# Digital_Input.net
KiCad netlist of a schematic drawn in Altium Designer
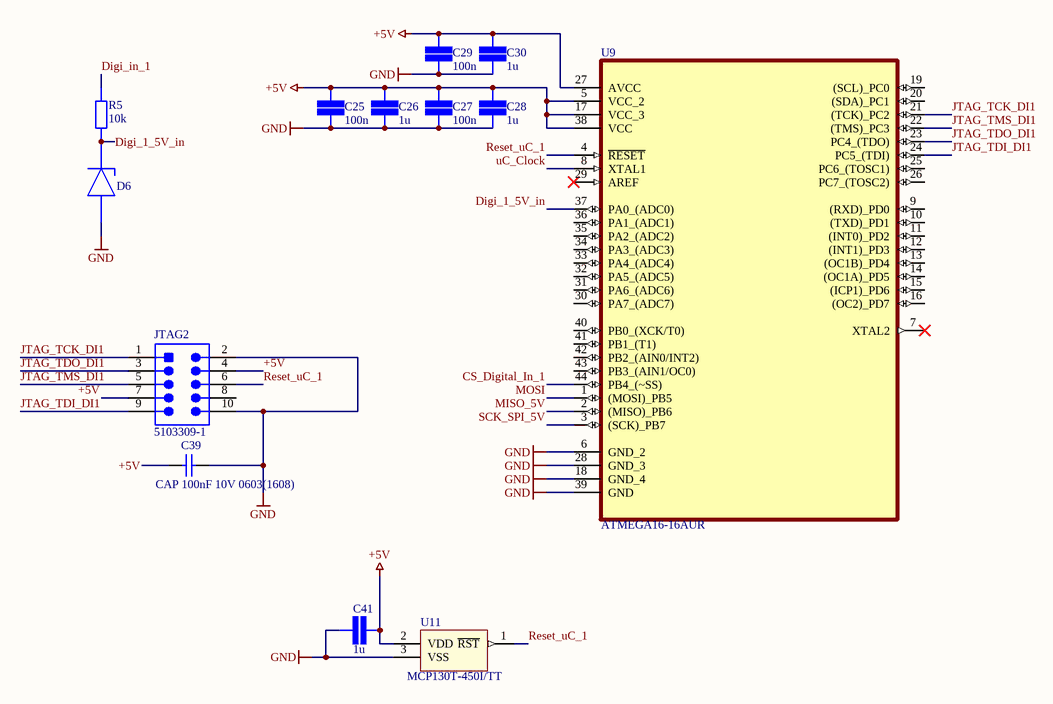
[diagram p0: Digital_Input.SchDoc]

(export (version "E")
  (design (tool "Eeschema 10.0.6"))
  (components
    (comp (ref "C25")
      (value "100n")
      (footprint "CAP 0603/1608")
      (description "Capacitor with multiple Footprints")
      (fields (field (name "Comment") "SMD Capacitor"))
      (libsource (lib "Standardbauteile") (part "SMD Capacitor"))
    )
    (comp (ref "C26")
      (value "1u")
      (footprint "CAP 0603/1608")
      (description "Capacitor with multiple Footprints")
      (fields (field (name "Comment") "SMD Capacitor"))
      (libsource (lib "Standardbauteile") (part "SMD Capacitor"))
    )
    (comp (ref "C27")
      (value "100n")
      (footprint "CAP 0603/1608")
      (description "Capacitor with multiple Footprints")
      (fields (field (name "Comment") "SMD Capacitor"))
      (libsource (lib "Standardbauteile") (part "SMD Capacitor"))
    )
    (comp (ref "C28")
      (value "1u")
      (footprint "CAP 0603/1608")
      (description "Capacitor with multiple Footprints")
      (fields (field (name "Comment") "SMD Capacitor"))
      (libsource (lib "Standardbauteile") (part "SMD Capacitor"))
    )
    (comp (ref "C29")
      (value "100n")
      (footprint "CAP 0603/1608")
      (description "Capacitor with multiple Footprints")
      (fields (field (name "Comment") "SMD Capacitor"))
      (libsource (lib "Standardbauteile") (part "SMD Capacitor"))
    )
    (comp (ref "C30")
      (value "1u")
      (footprint "CAP 0603/1608")
      (description "Capacitor with multiple Footprints")
      (fields (field (name "Comment") "SMD Capacitor"))
      (libsource (lib "Standardbauteile") (part "SMD Capacitor"))
    )
    (comp (ref "C39")
      (value "CAP 100nF 10V 0603(1608)")
      (footprint "CAPC0603(1608)100_L")
      (description "CAP 100nF 10V ±5% 0603 (1608 Metric) Thickness 1mm SMD")
      (fields (field (name "TOLERANCE") "Â±5%"))
      (libsource (lib "Altium Content Vault") (part "CAP"))
    )
    (comp (ref "C41")
      (value "1u")
      (footprint "CAP 0603/1608")
      (description "Capacitor with multiple Footprints")
      (fields (field (name "Comment") "SMD Capacitor"))
      (libsource (lib "") (part "SMD Capacitor_1"))
    )
    (comp (ref "D6")
      (value "MM3Z4V7T1G")
      (footprint "SOD-323-2")
      (description "onsemi MM3Z4V7T1G\r\nZ-Diode, 4,7V")
      (libsource (lib "libNico") (part "MM3Z4V7T1G"))
    )
    (comp (ref "JTAG2")
      (value "5103309-1")
      (footprint "TECO-5103309-1_V")
      (fields (field (name "MANUFACTURER") "TE Connectivity"))
      (libsource (lib "Altium Content Vault") (part "CN-2P-M-R10"))
    )
    (comp (ref "R5")
      (value "10k")
      (footprint "STACKPOLE CSR0603")
      (description "Resistor with multiple footprints")
      (fields (field (name "Comment") "SMD Resistor"))
      (libsource (lib "Standardbauteile") (part "SMD Resistor"))
    )
    (comp (ref "U9")
      (value "ATMEGA16-16AUR")
      (footprint "QFP80P1200X1200X120-44N")
      (description "8-bit Microcontroller")
      (libsource (lib "ATMEGA16-16AUR") (part "ATMEGA16-16AUR"))
    )
    (comp (ref "U11")
      (value "MCP130T-450I/TT")
      (footprint "*SOT95P237X112-3N")
      (description "System Supervisors - Power Supply Monitors with Reset Generators Open Drain Low")
      (fields (field (name "MF") "Microchip") (field (name "MP") "MCP120T-450I/TT"))
      (libsource (lib "Eric") (part "MCP130T-450I/TT"))
    )
  )
  (nets
    (net (code "1") (name "+5V") (class "Default")
      (node (ref "C25") (pin "2") (pinfunction "2_2") (pintype "passive"))
      (node (ref "C26") (pin "2") (pinfunction "2_2") (pintype "passive"))
      (node (ref "C27") (pin "2") (pinfunction "2_2") (pintype "passive"))
      (node (ref "C28") (pin "2") (pinfunction "2_2") (pintype "passive"))
      (node (ref "C29") (pin "2") (pinfunction "2_2") (pintype "passive"))
      (node (ref "C30") (pin "2") (pinfunction "2_2") (pintype "passive"))
      (node (ref "C39") (pin "1") (pinfunction "1_1") (pintype "passive"))
      (node (ref "C41") (pin "1") (pinfunction "1_1") (pintype "passive"))
      (node (ref "JTAG2") (pin "4") (pinfunction "4_4") (pintype "passive"))
      (node (ref "JTAG2") (pin "7") (pinfunction "7_7") (pintype "passive"))
      (node (ref "U11") (pin "2") (pinfunction "VDD_2") (pintype "power_in"))
      (node (ref "U9") (pin "17") (pinfunction "VCC_3_17") (pintype "power_in"))
      (node (ref "U9") (pin "27") (pinfunction "AVCC_27") (pintype "power_in"))
      (node (ref "U9") (pin "38") (pinfunction "VCC_38") (pintype "power_in"))
      (node (ref "U9") (pin "5") (pinfunction "VCC_2_5") (pintype "power_in"))
    )
    (net (code "2") (name "/CS_Digital_In_1") (class "Default")
      (node (ref "U9") (pin "44") (pinfunction "PB4_(~SS)_44") (pintype "bidirectional"))
    )
    (net (code "3") (name "/Digi_1_5V_in") (class "Default")
      (node (ref "D6") (pin "1C") (pinfunction "C_1C") (pintype "passive"))
      (node (ref "R5") (pin "2") (pinfunction "2_2") (pintype "passive"))
      (node (ref "U9") (pin "37") (pinfunction "PA0_(ADC0)_37") (pintype "bidirectional"))
    )
    (net (code "4") (name "/Digi_in_1") (class "Default")
      (node (ref "R5") (pin "1") (pinfunction "1_1") (pintype "passive"))
    )
    (net (code "5") (name "/JTAG_TCK_DI1") (class "Default")
      (node (ref "JTAG2") (pin "1") (pinfunction "1_1") (pintype "passive"))
      (node (ref "U9") (pin "21") (pinfunction "(TCK)_PC2_21") (pintype "bidirectional"))
    )
    (net (code "6") (name "/JTAG_TDI_DI1") (class "Default")
      (node (ref "JTAG2") (pin "9") (pinfunction "9_9") (pintype "passive"))
      (node (ref "U9") (pin "24") (pinfunction "PC5_(TDI)_24") (pintype "bidirectional"))
    )
    (net (code "7") (name "/JTAG_TDO_DI1") (class "Default")
      (node (ref "JTAG2") (pin "3") (pinfunction "3_3") (pintype "passive"))
      (node (ref "U9") (pin "23") (pinfunction "PC4_(TDO)_23") (pintype "bidirectional"))
    )
    (net (code "8") (name "/JTAG_TMS_DI1") (class "Default")
      (node (ref "JTAG2") (pin "5") (pinfunction "5_5") (pintype "passive"))
      (node (ref "U9") (pin "22") (pinfunction "(TMS)_PC3_22") (pintype "bidirectional"))
    )
    (net (code "9") (name "/MISO_5V") (class "Default")
      (node (ref "U9") (pin "2") (pinfunction "(MISO)_PB6_2") (pintype "bidirectional"))
    )
    (net (code "10") (name "/MOSI") (class "Default")
      (node (ref "U9") (pin "1") (pinfunction "(MOSI)_PB5_1") (pintype "bidirectional"))
    )
    (net (code "11") (name "/Reset_uC_1") (class "Default")
      (node (ref "JTAG2") (pin "6") (pinfunction "6_6") (pintype "passive"))
      (node (ref "U11") (pin "1") (pinfunction "~{RST}_1") (pintype "output"))
      (node (ref "U9") (pin "4") (pinfunction "~{RESET}_4") (pintype "input"))
    )
    (net (code "12") (name "/SCK_SPI_5V") (class "Default")
      (node (ref "U9") (pin "3") (pinfunction "(SCK)_PB7_3") (pintype "bidirectional"))
    )
    (net (code "13") (name "/uC_Clock") (class "Default")
      (node (ref "U9") (pin "8") (pinfunction "XTAL1_8") (pintype "input"))
    )
    (net (code "14") (name "GND") (class "Default")
      (node (ref "C25") (pin "1") (pinfunction "1_1") (pintype "passive"))
      (node (ref "C26") (pin "1") (pinfunction "1_1") (pintype "passive"))
      (node (ref "C27") (pin "1") (pinfunction "1_1") (pintype "passive"))
      (node (ref "C28") (pin "1") (pinfunction "1_1") (pintype "passive"))
      (node (ref "C29") (pin "1") (pinfunction "1_1") (pintype "passive"))
      (node (ref "C30") (pin "1") (pinfunction "1_1") (pintype "passive"))
      (node (ref "C39") (pin "2") (pinfunction "2_2") (pintype "passive"))
      (node (ref "C41") (pin "2") (pinfunction "2_2") (pintype "passive"))
      (node (ref "D6") (pin "2A") (pinfunction "A_2A") (pintype "passive"))
      (node (ref "JTAG2") (pin "10") (pinfunction "10_10") (pintype "passive"))
      (node (ref "JTAG2") (pin "2") (pinfunction "2_2") (pintype "passive"))
      (node (ref "U11") (pin "3") (pinfunction "VSS_3") (pintype "power_in"))
      (node (ref "U9") (pin "18") (pinfunction "GND_4_18") (pintype "passive"))
      (node (ref "U9") (pin "28") (pinfunction "GND_3_28") (pintype "passive"))
      (node (ref "U9") (pin "39") (pinfunction "GND_39") (pintype "passive"))
      (node (ref "U9") (pin "6") (pinfunction "GND_2_6") (pintype "passive"))
    )
    (net (code "15") (name "unconnected-(JTAG2-Pad8)") (class "Default")
      (node (ref "JTAG2") (pin "8") (pinfunction "8_8") (pintype "passive"))
    )
    (net (code "16") (name "unconnected-(U9-(ICP1)_PD6-Pad15)") (class "Default")
      (node (ref "U9") (pin "15") (pinfunction "(ICP1)_PD6_15") (pintype "bidirectional"))
    )
    (net (code "17") (name "unconnected-(U9-(INT0)_PD2-Pad11)") (class "Default")
      (node (ref "U9") (pin "11") (pinfunction "(INT0)_PD2_11") (pintype "bidirectional"))
    )
    (net (code "18") (name "unconnected-(U9-(INT1)_PD3-Pad12)") (class "Default")
      (node (ref "U9") (pin "12") (pinfunction "(INT1)_PD3_12") (pintype "bidirectional"))
    )
    (net (code "19") (name "unconnected-(U9-(OC1A)_PD5-Pad14)") (class "Default")
      (node (ref "U9") (pin "14") (pinfunction "(OC1A)_PD5_14") (pintype "bidirectional"))
    )
    (net (code "20") (name "unconnected-(U9-(OC1B)_PD4-Pad13)") (class "Default")
      (node (ref "U9") (pin "13") (pinfunction "(OC1B)_PD4_13") (pintype "bidirectional"))
    )
    (net (code "21") (name "unconnected-(U9-(OC2)_PD7-Pad16)") (class "Default")
      (node (ref "U9") (pin "16") (pinfunction "(OC2)_PD7_16") (pintype "bidirectional"))
    )
    (net (code "22") (name "unconnected-(U9-(RXD)_PD0-Pad9)") (class "Default")
      (node (ref "U9") (pin "9") (pinfunction "(RXD)_PD0_9") (pintype "bidirectional"))
    )
    (net (code "23") (name "unconnected-(U9-(SCL)_PC0-Pad19)") (class "Default")
      (node (ref "U9") (pin "19") (pinfunction "(SCL)_PC0_19") (pintype "bidirectional"))
    )
    (net (code "24") (name "unconnected-(U9-(SDA)_PC1-Pad20)") (class "Default")
      (node (ref "U9") (pin "20") (pinfunction "(SDA)_PC1_20") (pintype "bidirectional"))
    )
    (net (code "25") (name "unconnected-(U9-(TXD)_PD1-Pad10)") (class "Default")
      (node (ref "U9") (pin "10") (pinfunction "(TXD)_PD1_10") (pintype "bidirectional"))
    )
    (net (code "26") (name "unconnected-(U9-AREF-Pad29)") (class "Default")
      (node (ref "U9") (pin "29") (pinfunction "AREF_29") (pintype "input+no_connect"))
    )
    (net (code "27") (name "unconnected-(U9-PA1_(ADC1)-Pad36)") (class "Default")
      (node (ref "U9") (pin "36") (pinfunction "PA1_(ADC1)_36") (pintype "bidirectional"))
    )
    (net (code "28") (name "unconnected-(U9-PA2_(ADC2)-Pad35)") (class "Default")
      (node (ref "U9") (pin "35") (pinfunction "PA2_(ADC2)_35") (pintype "bidirectional"))
    )
    (net (code "29") (name "unconnected-(U9-PA3_(ADC3)-Pad34)") (class "Default")
      (node (ref "U9") (pin "34") (pinfunction "PA3_(ADC3)_34") (pintype "bidirectional"))
    )
    (net (code "30") (name "unconnected-(U9-PA4_(ADC4)-Pad33)") (class "Default")
      (node (ref "U9") (pin "33") (pinfunction "PA4_(ADC4)_33") (pintype "bidirectional"))
    )
    (net (code "31") (name "unconnected-(U9-PA5_(ADC5)-Pad32)") (class "Default")
      (node (ref "U9") (pin "32") (pinfunction "PA5_(ADC5)_32") (pintype "bidirectional"))
    )
    (net (code "32") (name "unconnected-(U9-PA6_(ADC6)-Pad31)") (class "Default")
      (node (ref "U9") (pin "31") (pinfunction "PA6_(ADC6)_31") (pintype "bidirectional"))
    )
    (net (code "33") (name "unconnected-(U9-PA7_(ADC7)-Pad30)") (class "Default")
      (node (ref "U9") (pin "30") (pinfunction "PA7_(ADC7)_30") (pintype "bidirectional"))
    )
    (net (code "34") (name "unconnected-(U9-PB0_(XCK{slash}T0)-Pad40)") (class "Default")
      (node (ref "U9") (pin "40") (pinfunction "PB0_(XCK/T0)_40") (pintype "bidirectional"))
    )
    (net (code "35") (name "unconnected-(U9-PB1_(T1)-Pad41)") (class "Default")
      (node (ref "U9") (pin "41") (pinfunction "PB1_(T1)_41") (pintype "bidirectional"))
    )
    (net (code "36") (name "unconnected-(U9-PB2_(AIN0{slash}INT2)-Pad42)") (class "Default")
      (node (ref "U9") (pin "42") (pinfunction "PB2_(AIN0/INT2)_42") (pintype "bidirectional"))
    )
    (net (code "37") (name "unconnected-(U9-PB3_(AIN1{slash}OC0)-Pad43)") (class "Default")
      (node (ref "U9") (pin "43") (pinfunction "PB3_(AIN1/OC0)_43") (pintype "bidirectional"))
    )
    (net (code "38") (name "unconnected-(U9-PC6_(TOSC1)-Pad25)") (class "Default")
      (node (ref "U9") (pin "25") (pinfunction "PC6_(TOSC1)_25") (pintype "bidirectional"))
    )
    (net (code "39") (name "unconnected-(U9-PC7_(TOSC2)-Pad26)") (class "Default")
      (node (ref "U9") (pin "26") (pinfunction "PC7_(TOSC2)_26") (pintype "bidirectional"))
    )
    (net (code "40") (name "unconnected-(U9-XTAL2-Pad7)") (class "Default")
      (node (ref "U9") (pin "7") (pinfunction "XTAL2_7") (pintype "output+no_connect"))
    )
  )
)
